# MAGI_sDIPBoard-MBH.net
KiCad netlist of a schematic drawn in Altium Designer
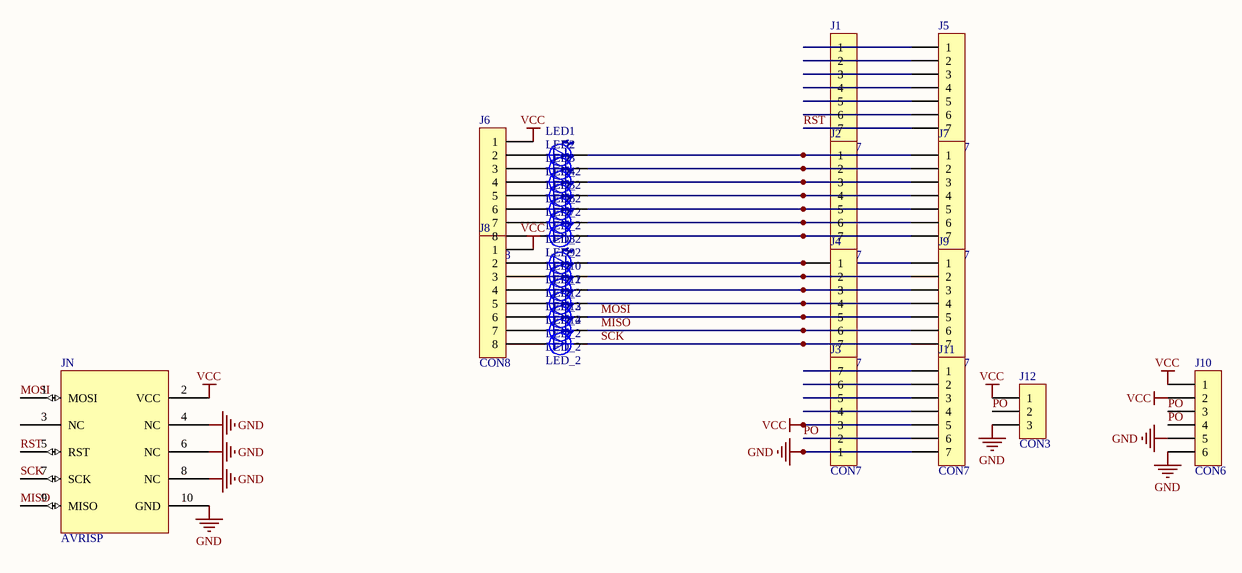
[diagram p0: MAGI'sDIPBoard-MBH.SchDoc]

(export (version "E")
  (design (tool "Eeschema 10.0.6"))
  (components
    (comp (ref "J1")
      (value "CON7")
      (footprint "CON7")
      (description "Connector")
      (libsource (lib "CON系列") (part "CON7"))
    )
    (comp (ref "J2")
      (value "CON7")
      (footprint "CON7")
      (description "Connector")
      (libsource (lib "CON系列") (part "CON7"))
    )
    (comp (ref "J3")
      (value "CON7")
      (footprint "CON7")
      (description "Connector")
      (libsource (lib "") (part "CON7_1"))
    )
    (comp (ref "J4")
      (value "CON7")
      (footprint "CON7")
      (description "Connector")
      (libsource (lib "CON系列") (part "CON7"))
    )
    (comp (ref "J5")
      (value "CON7")
      (footprint "CON7")
      (description "Connector")
      (libsource (lib "CON系列") (part "CON7"))
    )
    (comp (ref "J6")
      (value "CON8")
      (footprint "CON8")
      (description "Connector")
      (libsource (lib "CON系列") (part "CON8"))
    )
    (comp (ref "J7")
      (value "CON7")
      (footprint "CON7")
      (description "Connector")
      (libsource (lib "CON系列") (part "CON7"))
    )
    (comp (ref "J8")
      (value "CON8")
      (footprint "CON8")
      (description "Connector")
      (libsource (lib "CON系列") (part "CON8"))
    )
    (comp (ref "J9")
      (value "CON7")
      (footprint "CON7")
      (description "Connector")
      (libsource (lib "CON系列") (part "CON7"))
    )
    (comp (ref "J10")
      (value "CON6")
      (footprint "CON6")
      (description "Connector")
      (libsource (lib "CON系列") (part "CON6"))
    )
    (comp (ref "J11")
      (value "CON7")
      (footprint "CON7")
      (description "Connector")
      (libsource (lib "CON系列") (part "CON7"))
    )
    (comp (ref "J12")
      (value "CON3")
      (footprint "CON3")
      (description "Connector")
      (libsource (lib "CON系列") (part "CON3"))
    )
    (comp (ref "JN") (value "AVRISP") (footprint "AVRISP") (libsource (lib "AVRISP") (part "AVRISP")))
    (comp (ref "LED1") (value "LED_2") (footprint "LED5") (libsource (lib "二极管") (part "LED_2")))
    (comp (ref "LED2") (value "LED_2") (footprint "LED5") (libsource (lib "二极管") (part "LED_2")))
    (comp (ref "LED3") (value "LED_2") (footprint "LED5") (libsource (lib "二极管") (part "LED_2")))
    (comp (ref "LED4") (value "LED_2") (footprint "LED5") (libsource (lib "二极管") (part "LED_2")))
    (comp (ref "LED5") (value "LED_2") (footprint "LED5") (libsource (lib "二极管") (part "LED_2")))
    (comp (ref "LED6") (value "LED_2") (footprint "LED5") (libsource (lib "二极管") (part "LED_2")))
    (comp (ref "LED7") (value "LED_2") (footprint "LED5") (libsource (lib "二极管") (part "LED_2")))
    (comp (ref "LED8") (value "LED_2") (footprint "LED5") (libsource (lib "二极管") (part "LED_2")))
    (comp (ref "LED9") (value "LED_2") (footprint "LED5") (libsource (lib "二极管") (part "LED_2")))
    (comp (ref "LED10") (value "LED_2") (footprint "LED5") (libsource (lib "二极管") (part "LED_2")))
    (comp (ref "LED11") (value "LED_2") (footprint "LED5") (libsource (lib "二极管") (part "LED_2")))
    (comp (ref "LED12") (value "LED_2") (footprint "LED5") (libsource (lib "二极管") (part "LED_2")))
    (comp (ref "LED13") (value "LED_2") (footprint "LED5") (libsource (lib "二极管") (part "LED_2")))
    (comp (ref "LED14") (value "LED_2") (footprint "LED5") (libsource (lib "二极管") (part "LED_2")))
  )
  (nets
    (net (code "1") (name "/MISO") (class "Default")
      (node (ref "J4") (pin "6") (pinfunction "6_6") (pintype "passive"))
      (node (ref "J9") (pin "6") (pinfunction "6_6") (pintype "passive"))
      (node (ref "JN") (pin "9") (pinfunction "MISO_9") (pintype "bidirectional"))
      (node (ref "LED13") (pin "K") (pinfunction "K_K") (pintype "passive"))
    )
    (net (code "2") (name "/MOSI") (class "Default")
      (node (ref "J4") (pin "5") (pinfunction "5_5") (pintype "passive"))
      (node (ref "J9") (pin "5") (pinfunction "5_5") (pintype "passive"))
      (node (ref "JN") (pin "1") (pinfunction "MOSI_1") (pintype "bidirectional"))
      (node (ref "LED12") (pin "K") (pinfunction "K_K") (pintype "passive"))
    )
    (net (code "3") (name "/PO") (class "Default")
      (node (ref "J10") (pin "3") (pinfunction "3_3") (pintype "passive"))
      (node (ref "J10") (pin "4") (pinfunction "4_4") (pintype "passive"))
      (node (ref "J11") (pin "6") (pinfunction "6_6") (pintype "passive"))
      (node (ref "J12") (pin "2") (pinfunction "2_2") (pintype "passive"))
      (node (ref "J3") (pin "2") (pinfunction "2_2") (pintype "passive"))
    )
    (net (code "4") (name "/RST") (class "Default")
      (node (ref "J1") (pin "7") (pinfunction "7_7") (pintype "passive"))
      (node (ref "J5") (pin "7") (pinfunction "7_7") (pintype "passive"))
      (node (ref "JN") (pin "5") (pinfunction "RST_5") (pintype "bidirectional"))
    )
    (net (code "5") (name "/SCK") (class "Default")
      (node (ref "J4") (pin "7") (pinfunction "7_7") (pintype "passive"))
      (node (ref "J9") (pin "7") (pinfunction "7_7") (pintype "passive"))
      (node (ref "JN") (pin "7") (pinfunction "SCK_7") (pintype "bidirectional"))
      (node (ref "LED14") (pin "K") (pinfunction "K_K") (pintype "passive"))
    )
    (net (code "6") (name "GND") (class "Default")
      (node (ref "J10") (pin "5") (pinfunction "5_5") (pintype "passive"))
      (node (ref "J10") (pin "6") (pinfunction "6_6") (pintype "passive"))
      (node (ref "J11") (pin "7") (pinfunction "7_7") (pintype "passive"))
      (node (ref "J12") (pin "3") (pinfunction "3_3") (pintype "passive"))
      (node (ref "J3") (pin "1") (pinfunction "1_1") (pintype "passive"))
      (node (ref "JN") (pin "10") (pinfunction "GND_10") (pintype "power_in"))
      (node (ref "JN") (pin "4") (pinfunction "NC_4") (pintype "power_in"))
      (node (ref "JN") (pin "6") (pinfunction "NC_6") (pintype "power_in"))
      (node (ref "JN") (pin "8") (pinfunction "NC_8") (pintype "power_in"))
    )
    (net (code "7") (name "Net-(J1-Pad1)") (class "Default")
      (node (ref "J1") (pin "1") (pinfunction "1_1") (pintype "passive"))
      (node (ref "J5") (pin "1") (pinfunction "1_1") (pintype "passive"))
    )
    (net (code "8") (name "Net-(J1-Pad2)") (class "Default")
      (node (ref "J1") (pin "2") (pinfunction "2_2") (pintype "passive"))
      (node (ref "J5") (pin "2") (pinfunction "2_2") (pintype "passive"))
    )
    (net (code "9") (name "Net-(J1-Pad3)") (class "Default")
      (node (ref "J1") (pin "3") (pinfunction "3_3") (pintype "passive"))
      (node (ref "J5") (pin "3") (pinfunction "3_3") (pintype "passive"))
    )
    (net (code "10") (name "Net-(J1-Pad4)") (class "Default")
      (node (ref "J1") (pin "4") (pinfunction "4_4") (pintype "passive"))
      (node (ref "J5") (pin "4") (pinfunction "4_4") (pintype "passive"))
    )
    (net (code "11") (name "Net-(J1-Pad5)") (class "Default")
      (node (ref "J1") (pin "5") (pinfunction "5_5") (pintype "passive"))
      (node (ref "J5") (pin "5") (pinfunction "5_5") (pintype "passive"))
    )
    (net (code "12") (name "Net-(J1-Pad6)") (class "Default")
      (node (ref "J1") (pin "6") (pinfunction "6_6") (pintype "passive"))
      (node (ref "J5") (pin "6") (pinfunction "6_6") (pintype "passive"))
    )
    (net (code "13") (name "Net-(J2-Pad1)") (class "Default")
      (node (ref "J2") (pin "1") (pinfunction "1_1") (pintype "passive"))
      (node (ref "J7") (pin "1") (pinfunction "1_1") (pintype "passive"))
      (node (ref "LED1") (pin "K") (pinfunction "K_K") (pintype "passive"))
    )
    (net (code "14") (name "Net-(J2-Pad2)") (class "Default")
      (node (ref "J2") (pin "2") (pinfunction "2_2") (pintype "passive"))
      (node (ref "J7") (pin "2") (pinfunction "2_2") (pintype "passive"))
      (node (ref "LED2") (pin "K") (pinfunction "K_K") (pintype "passive"))
    )
    (net (code "15") (name "Net-(J2-Pad3)") (class "Default")
      (node (ref "J2") (pin "3") (pinfunction "3_3") (pintype "passive"))
      (node (ref "J7") (pin "3") (pinfunction "3_3") (pintype "passive"))
      (node (ref "LED3") (pin "K") (pinfunction "K_K") (pintype "passive"))
    )
    (net (code "16") (name "Net-(J2-Pad4)") (class "Default")
      (node (ref "J2") (pin "4") (pinfunction "4_4") (pintype "passive"))
      (node (ref "J7") (pin "4") (pinfunction "4_4") (pintype "passive"))
      (node (ref "LED4") (pin "K") (pinfunction "K_K") (pintype "passive"))
    )
    (net (code "17") (name "Net-(J2-Pad5)") (class "Default")
      (node (ref "J2") (pin "5") (pinfunction "5_5") (pintype "passive"))
      (node (ref "J7") (pin "5") (pinfunction "5_5") (pintype "passive"))
      (node (ref "LED5") (pin "K") (pinfunction "K_K") (pintype "passive"))
    )
    (net (code "18") (name "Net-(J2-Pad6)") (class "Default")
      (node (ref "J2") (pin "6") (pinfunction "6_6") (pintype "passive"))
      (node (ref "J7") (pin "6") (pinfunction "6_6") (pintype "passive"))
      (node (ref "LED6") (pin "K") (pinfunction "K_K") (pintype "passive"))
    )
    (net (code "19") (name "Net-(J2-Pad7)") (class "Default")
      (node (ref "J2") (pin "7") (pinfunction "7_7") (pintype "passive"))
      (node (ref "J7") (pin "7") (pinfunction "7_7") (pintype "passive"))
      (node (ref "LED7") (pin "K") (pinfunction "K_K") (pintype "passive"))
    )
    (net (code "20") (name "Net-(J4-Pad1)") (class "Default")
      (node (ref "J4") (pin "1") (pinfunction "1_1") (pintype "passive"))
      (node (ref "J9") (pin "1") (pinfunction "1_1") (pintype "passive"))
      (node (ref "LED8") (pin "K") (pinfunction "K_K") (pintype "passive"))
    )
    (net (code "21") (name "Net-(J4-Pad2)") (class "Default")
      (node (ref "J4") (pin "2") (pinfunction "2_2") (pintype "passive"))
      (node (ref "J9") (pin "2") (pinfunction "2_2") (pintype "passive"))
      (node (ref "LED9") (pin "K") (pinfunction "K_K") (pintype "passive"))
    )
    (net (code "22") (name "Net-(J4-Pad3)") (class "Default")
      (node (ref "J4") (pin "3") (pinfunction "3_3") (pintype "passive"))
      (node (ref "J9") (pin "3") (pinfunction "3_3") (pintype "passive"))
      (node (ref "LED10") (pin "K") (pinfunction "K_K") (pintype "passive"))
    )
    (net (code "23") (name "Net-(J4-Pad4)") (class "Default")
      (node (ref "J4") (pin "4") (pinfunction "4_4") (pintype "passive"))
      (node (ref "J9") (pin "4") (pinfunction "4_4") (pintype "passive"))
      (node (ref "LED11") (pin "K") (pinfunction "K_K") (pintype "passive"))
    )
    (net (code "24") (name "Net-(J6-Pad2)") (class "Default")
      (node (ref "J6") (pin "2") (pinfunction "2_2") (pintype "passive"))
      (node (ref "LED1") (pin "A") (pinfunction "A_A") (pintype "passive"))
    )
    (net (code "25") (name "Net-(J6-Pad3)") (class "Default")
      (node (ref "J6") (pin "3") (pinfunction "3_3") (pintype "passive"))
      (node (ref "LED2") (pin "A") (pinfunction "A_A") (pintype "passive"))
    )
    (net (code "26") (name "Net-(J6-Pad4)") (class "Default")
      (node (ref "J6") (pin "4") (pinfunction "4_4") (pintype "passive"))
      (node (ref "LED3") (pin "A") (pinfunction "A_A") (pintype "passive"))
    )
    (net (code "27") (name "Net-(J6-Pad5)") (class "Default")
      (node (ref "J6") (pin "5") (pinfunction "5_5") (pintype "passive"))
      (node (ref "LED4") (pin "A") (pinfunction "A_A") (pintype "passive"))
    )
    (net (code "28") (name "Net-(J6-Pad6)") (class "Default")
      (node (ref "J6") (pin "6") (pinfunction "6_6") (pintype "passive"))
      (node (ref "LED5") (pin "A") (pinfunction "A_A") (pintype "passive"))
    )
    (net (code "29") (name "Net-(J6-Pad7)") (class "Default")
      (node (ref "J6") (pin "7") (pinfunction "7_7") (pintype "passive"))
      (node (ref "LED6") (pin "A") (pinfunction "A_A") (pintype "passive"))
    )
    (net (code "30") (name "Net-(J6-Pad8)") (class "Default")
      (node (ref "J6") (pin "8") (pinfunction "8_8") (pintype "passive"))
      (node (ref "LED7") (pin "A") (pinfunction "A_A") (pintype "passive"))
    )
    (net (code "31") (name "Net-(J8-Pad2)") (class "Default")
      (node (ref "J8") (pin "2") (pinfunction "2_2") (pintype "passive"))
      (node (ref "LED8") (pin "A") (pinfunction "A_A") (pintype "passive"))
    )
    (net (code "32") (name "Net-(J8-Pad3)") (class "Default")
      (node (ref "J8") (pin "3") (pinfunction "3_3") (pintype "passive"))
      (node (ref "LED9") (pin "A") (pinfunction "A_A") (pintype "passive"))
    )
    (net (code "33") (name "Net-(J8-Pad4)") (class "Default")
      (node (ref "J8") (pin "4") (pinfunction "4_4") (pintype "passive"))
      (node (ref "LED10") (pin "A") (pinfunction "A_A") (pintype "passive"))
    )
    (net (code "34") (name "Net-(J8-Pad5)") (class "Default")
      (node (ref "J8") (pin "5") (pinfunction "5_5") (pintype "passive"))
      (node (ref "LED11") (pin "A") (pinfunction "A_A") (pintype "passive"))
    )
    (net (code "35") (name "Net-(J8-Pad6)") (class "Default")
      (node (ref "J8") (pin "6") (pinfunction "6_6") (pintype "passive"))
      (node (ref "LED12") (pin "A") (pinfunction "A_A") (pintype "passive"))
    )
    (net (code "36") (name "Net-(J8-Pad7)") (class "Default")
      (node (ref "J8") (pin "7") (pinfunction "7_7") (pintype "passive"))
      (node (ref "LED13") (pin "A") (pinfunction "A_A") (pintype "passive"))
    )
    (net (code "37") (name "Net-(J8-Pad8)") (class "Default")
      (node (ref "J8") (pin "8") (pinfunction "8_8") (pintype "passive"))
      (node (ref "LED14") (pin "A") (pinfunction "A_A") (pintype "passive"))
    )
    (net (code "38") (name "Net-(J11-Pad1)") (class "Default")
      (node (ref "J11") (pin "1") (pinfunction "1_1") (pintype "passive"))
      (node (ref "J3") (pin "7") (pinfunction "7_7") (pintype "passive"))
    )
    (net (code "39") (name "Net-(J11-Pad2)") (class "Default")
      (node (ref "J11") (pin "2") (pinfunction "2_2") (pintype "passive"))
      (node (ref "J3") (pin "6") (pinfunction "6_6") (pintype "passive"))
    )
    (net (code "40") (name "Net-(J11-Pad3)") (class "Default")
      (node (ref "J11") (pin "3") (pinfunction "3_3") (pintype "passive"))
      (node (ref "J3") (pin "5") (pinfunction "5_5") (pintype "passive"))
    )
    (net (code "41") (name "Net-(J11-Pad4)") (class "Default")
      (node (ref "J11") (pin "4") (pinfunction "4_4") (pintype "passive"))
      (node (ref "J3") (pin "4") (pinfunction "4_4") (pintype "passive"))
    )
    (net (code "42") (name "VCC") (class "Default")
      (node (ref "J10") (pin "1") (pinfunction "1_1") (pintype "passive"))
      (node (ref "J10") (pin "2") (pinfunction "2_2") (pintype "passive"))
      (node (ref "J11") (pin "5") (pinfunction "5_5") (pintype "passive"))
      (node (ref "J12") (pin "1") (pinfunction "1_1") (pintype "passive"))
      (node (ref "J3") (pin "3") (pinfunction "3_3") (pintype "passive"))
      (node (ref "J6") (pin "1") (pinfunction "1_1") (pintype "passive"))
      (node (ref "J8") (pin "1") (pinfunction "1_1") (pintype "passive"))
      (node (ref "JN") (pin "2") (pinfunction "VCC_2") (pintype "power_in"))
    )
    (net (code "43") (name "unconnected-(JN-NC-Pad3)") (class "Default")
      (node (ref "JN") (pin "3") (pinfunction "NC_3") (pintype "power_in"))
    )
  )
)
